# voltage-amplifier.net
KiCad netlist of a schematic drawn in EAGLE
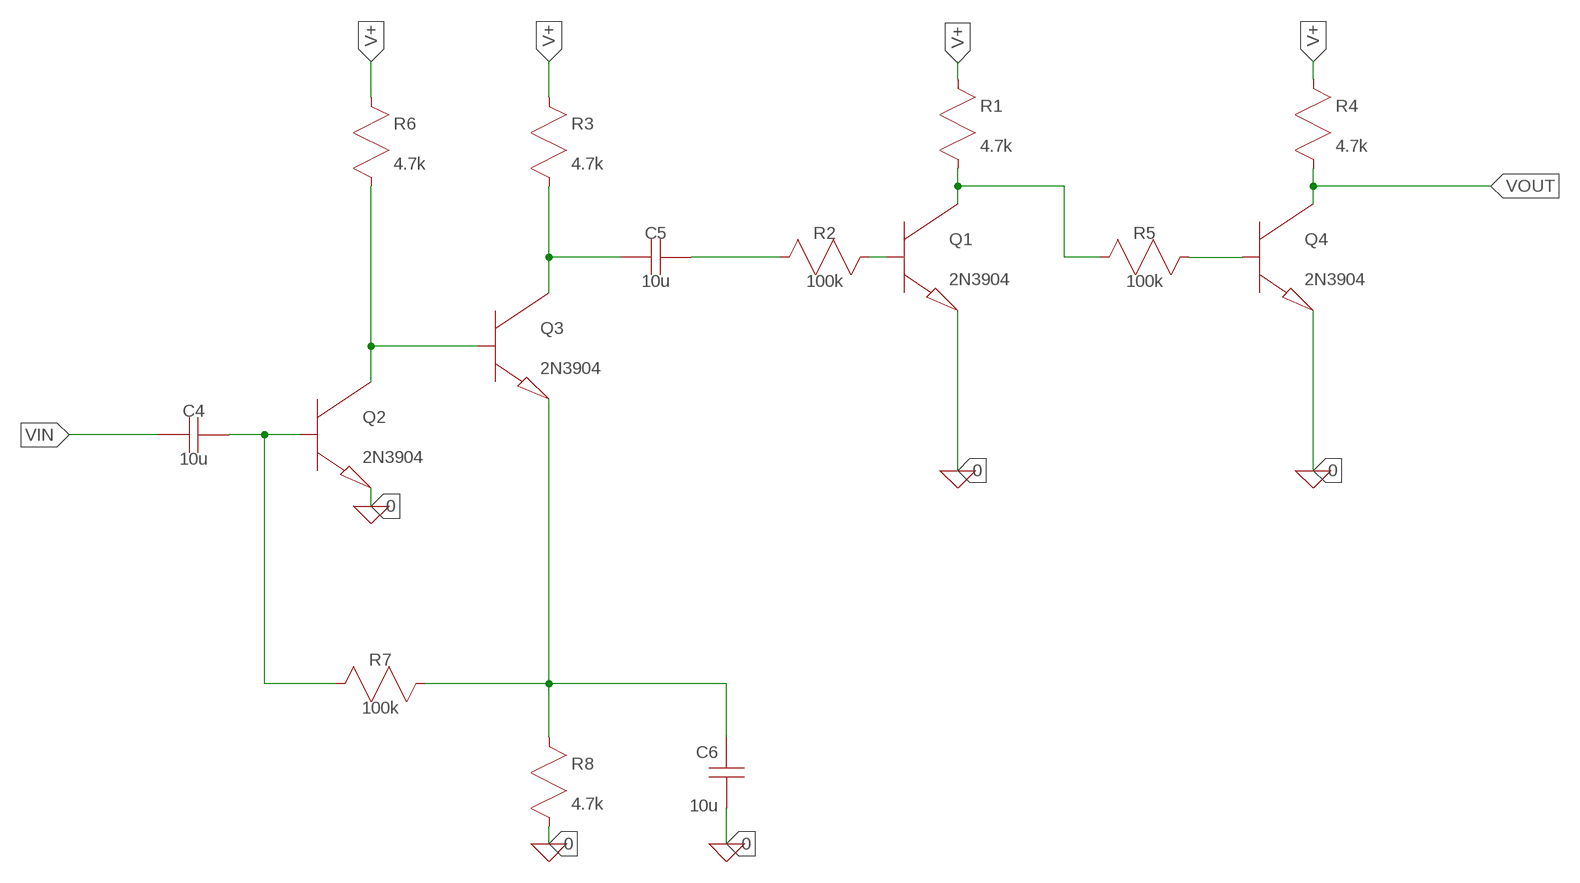
[diagram p0: schematic, sheet 1]

(export (version "E")
  (design (tool "Eeschema 10.0.6"))
  (components
    (comp (ref "C4")
      (value "10u")
      (footprint "eagle-import:C050-025X075")
      (libsource (lib "eagle-import") (part "CAP"))
    )
    (comp (ref "C5")
      (value "10u")
      (footprint "eagle-import:C050-025X075")
      (libsource (lib "eagle-import") (part "CAP"))
    )
    (comp (ref "C6")
      (value "10u")
      (footprint "eagle-import:C050-025X075")
      (libsource (lib "eagle-import") (part "CAP"))
    )
    (comp (ref "Q1")
      (value "2N3904")
      (footprint "eagle-import:TO92")
      (libsource (lib "eagle-import") (part "NPN"))
    )
    (comp (ref "Q2")
      (value "2N3904")
      (footprint "eagle-import:TO92")
      (libsource (lib "eagle-import") (part "NPN"))
    )
    (comp (ref "Q3")
      (value "2N3904")
      (footprint "eagle-import:TO92")
      (libsource (lib "eagle-import") (part "NPN"))
    )
    (comp (ref "Q4")
      (value "2N3904")
      (footprint "eagle-import:TO92")
      (libsource (lib "eagle-import") (part "NPN"))
    )
    (comp (ref "R1")
      (value "4.7k")
      (footprint "eagle-import:0207_7")
      (libsource (lib "eagle-import") (part "RES"))
    )
    (comp (ref "R2")
      (value "100k")
      (footprint "eagle-import:0309_10")
      (libsource (lib "eagle-import") (part "RES'0309'"))
    )
    (comp (ref "R3")
      (value "4.7k")
      (footprint "eagle-import:0207_7")
      (libsource (lib "eagle-import") (part "RES"))
    )
    (comp (ref "R4")
      (value "4.7k")
      (footprint "eagle-import:0207_7")
      (libsource (lib "eagle-import") (part "RES"))
    )
    (comp (ref "R5")
      (value "100k")
      (footprint "eagle-import:0309_10")
      (libsource (lib "eagle-import") (part "RES'0309'"))
    )
    (comp (ref "R6")
      (value "4.7k")
      (footprint "eagle-import:0207_7")
      (libsource (lib "eagle-import") (part "RES"))
    )
    (comp (ref "R7")
      (value "100k")
      (footprint "eagle-import:0309_10")
      (libsource (lib "eagle-import") (part "RES'0309'"))
    )
    (comp (ref "R8")
      (value "4.7k")
      (footprint "eagle-import:0207_7")
      (libsource (lib "eagle-import") (part "RES"))
    )
  )
  (nets
    (net (code "1") (name "0") (class "Default")
      (node (ref "C6") (pin "1") (pinfunction "A_1") (pintype "passive"))
      (node (ref "Q1") (pin "1") (pinfunction "E_1") (pintype "passive"))
      (node (ref "Q2") (pin "1") (pinfunction "E_1") (pintype "passive"))
      (node (ref "Q4") (pin "1") (pinfunction "E_1") (pintype "passive"))
      (node (ref "R8") (pin "2") (pinfunction "B_2") (pintype "passive"))
    )
    (net (code "2") (name "Net-(C4-A)") (class "Default")
      (node (ref "C4") (pin "1") (pinfunction "A_1") (pintype "passive"))
      (node (ref "Q2") (pin "2") (pinfunction "B_2") (pintype "passive"))
      (node (ref "R7") (pin "2") (pinfunction "B_2") (pintype "passive"))
    )
    (net (code "3") (name "Net-(C5-A)") (class "Default")
      (node (ref "C5") (pin "1") (pinfunction "A_1") (pintype "passive"))
      (node (ref "R2") (pin "2") (pinfunction "B_2") (pintype "passive"))
    )
    (net (code "4") (name "Net-(C5-B)") (class "Default")
      (node (ref "C5") (pin "2") (pinfunction "B_2") (pintype "passive"))
      (node (ref "Q3") (pin "3") (pinfunction "C_3") (pintype "passive"))
      (node (ref "R3") (pin "2") (pinfunction "B_2") (pintype "passive"))
    )
    (net (code "5") (name "Net-(C6-B)") (class "Default")
      (node (ref "C6") (pin "2") (pinfunction "B_2") (pintype "passive"))
      (node (ref "Q3") (pin "1") (pinfunction "E_1") (pintype "passive"))
      (node (ref "R7") (pin "1") (pinfunction "A_1") (pintype "passive"))
      (node (ref "R8") (pin "1") (pinfunction "A_1") (pintype "passive"))
    )
    (net (code "6") (name "Net-(Q1-B)") (class "Default")
      (node (ref "Q1") (pin "2") (pinfunction "B_2") (pintype "passive"))
      (node (ref "R2") (pin "1") (pinfunction "A_1") (pintype "passive"))
    )
    (net (code "7") (name "Net-(Q1-C)") (class "Default")
      (node (ref "Q1") (pin "3") (pinfunction "C_3") (pintype "passive"))
      (node (ref "R1") (pin "2") (pinfunction "B_2") (pintype "passive"))
      (node (ref "R5") (pin "2") (pinfunction "B_2") (pintype "passive"))
    )
    (net (code "8") (name "Net-(Q2-C)") (class "Default")
      (node (ref "Q2") (pin "3") (pinfunction "C_3") (pintype "passive"))
      (node (ref "Q3") (pin "2") (pinfunction "B_2") (pintype "passive"))
      (node (ref "R6") (pin "2") (pinfunction "B_2") (pintype "passive"))
    )
    (net (code "9") (name "Net-(Q4-B)") (class "Default")
      (node (ref "Q4") (pin "2") (pinfunction "B_2") (pintype "passive"))
      (node (ref "R5") (pin "1") (pinfunction "A_1") (pintype "passive"))
    )
    (net (code "10") (name "V+") (class "Default")
      (node (ref "R1") (pin "1") (pinfunction "A_1") (pintype "passive"))
      (node (ref "R3") (pin "1") (pinfunction "A_1") (pintype "passive"))
      (node (ref "R4") (pin "1") (pinfunction "A_1") (pintype "passive"))
      (node (ref "R6") (pin "1") (pinfunction "A_1") (pintype "passive"))
    )
    (net (code "11") (name "VIN") (class "Default")
      (node (ref "C4") (pin "2") (pinfunction "B_2") (pintype "passive"))
    )
    (net (code "12") (name "VOUT") (class "Default")
      (node (ref "Q4") (pin "3") (pinfunction "C_3") (pintype "passive"))
      (node (ref "R4") (pin "2") (pinfunction "B_2") (pintype "passive"))
    )
  )
)
